# Switches.net
KiCad netlist of a schematic drawn in Altium Designer
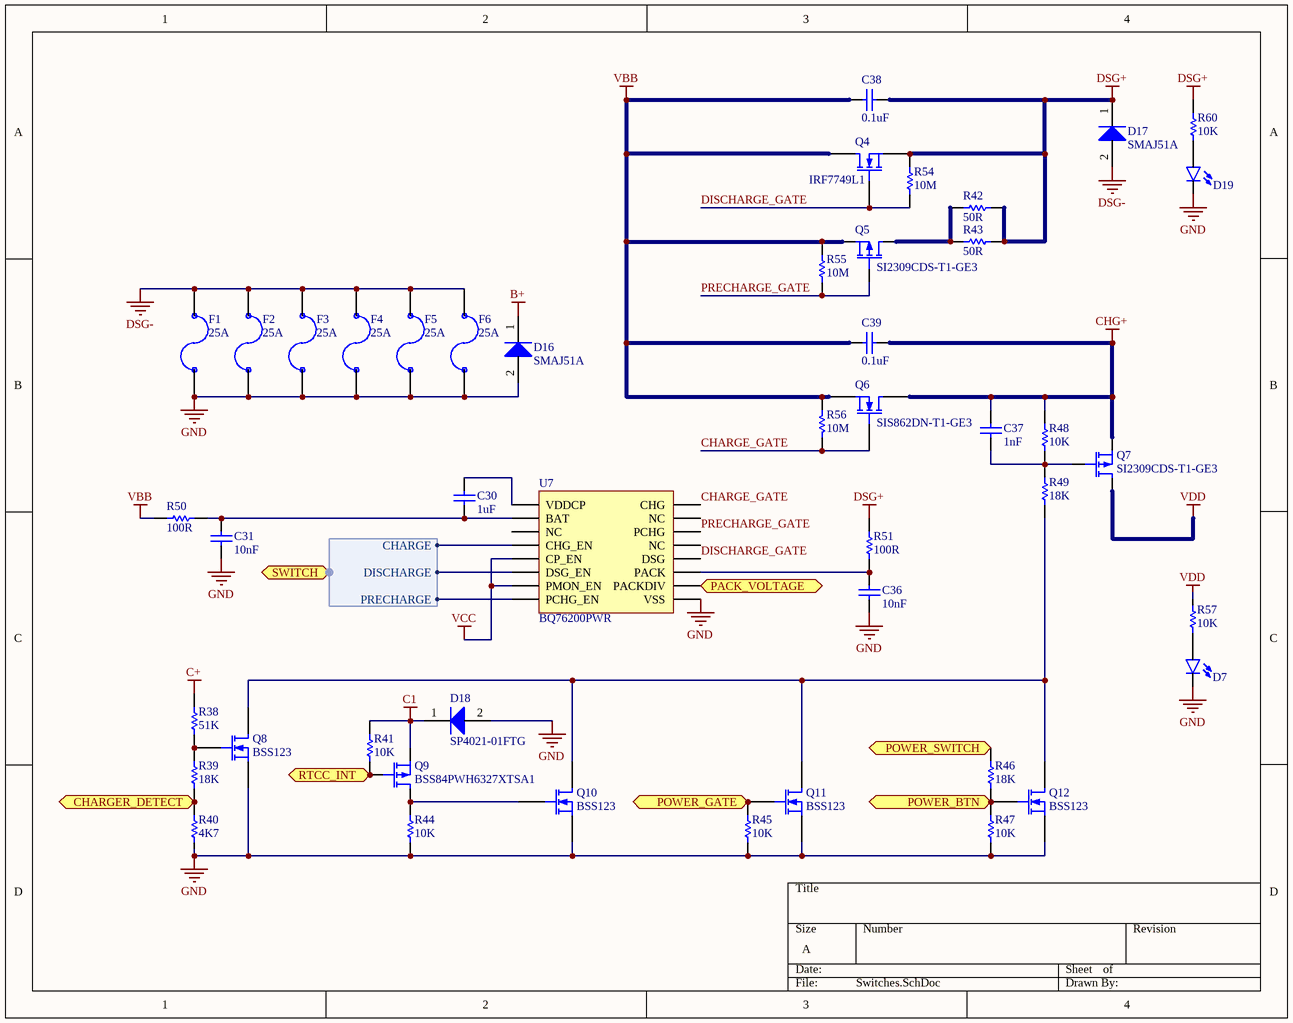
[diagram p0: Switches.SchDoc]

(export (version "E")
  (design (tool "Eeschema 10.0.6"))
  (components
    (comp (ref "C30")
      (value "1uF")
      (footprint "C0603[1608X92]")
      (description "1uF 50V 10% 0603 (1608 Metric)")
      (fields (field (name "TOLERANCE") "10%") (field (name "PARTNUMBER") "GRM188R61H105KAALD"))
      (libsource (lib "Capacitors") (part "CAP_1uF_50V_0603_10%"))
    )
    (comp (ref "C31")
      (value "10nF")
      (footprint "C0402[1005X55]")
      (description "10nF 100V 10% 0402 (1005 Metric)")
      (fields (field (name "TOLERANCE") "10%") (field (name "PARTNUMBER") "C1005X7S2A103K050BB"))
      (libsource (lib "Capacitors") (part "CAP_10nF_100V_0402_10%"))
    )
    (comp (ref "C36")
      (value "10nF")
      (footprint "C0402[1005X55]")
      (description "10nF 100V 10% 0402 (1005 Metric)")
      (fields (field (name "TOLERANCE") "10%") (field (name "PARTNUMBER") "C1005X7S2A103K050BB"))
      (libsource (lib "Capacitors") (part "CAP_10nF_100V_0402_10%"))
    )
    (comp (ref "C37")
      (value "1nF")
      (footprint "C0402[1005X55]")
      (description "1nF 50V 5% 0402 (1005 Metric)")
      (fields (field (name "PARTNUMBER") "GRM1555C1H102JA01D") (field (name "MANUFACTURER") "Murata"))
      (libsource (lib "Capacitors") (part "CAP_1nF_50V_0402_5%"))
    )
    (comp (ref "C38")
      (value "0.1uF")
      (footprint "C0402[1005X55]")
      (description "0.1uF 100V 10% 0402 (1005 Metric)")
      (fields (field (name "PARTNUMBER") "GRM155R62A104KE14D") (field (name "MANUFACTURER") "Murata"))
      (libsource (lib "Capacitors") (part "CAP_0.1uF_100V_0402_10%"))
    )
    (comp (ref "C39")
      (value "0.1uF")
      (footprint "C0402[1005X55]")
      (description "0.1uF 100V 10% 0402 (1005 Metric)")
      (fields (field (name "PARTNUMBER") "GRM155R62A104KE14D") (field (name "MANUFACTURER") "Murata"))
      (libsource (lib "Capacitors") (part "CAP_0.1uF_100V_0402_10%"))
    )
    (comp (ref "D7")
      (value "LED-BLUE")
      (footprint "LED0603")
      (fields (field (name "PARTNUMBER") "LTST-C193TGKT-5A") (field (name "MANUFACTURER") "Lite-On Inc."))
      (libsource (lib "LEDs") (part "LED_0603_GREEN_5mA"))
    )
    (comp (ref "D16")
      (value "SMAJ51A")
      (footprint "DO-214AC")
      (fields (field (name "PARTNUMBER") "SMAJ51A-E3/61") (field (name "MANUFACTURER") "Vishay"))
      (libsource (lib "Diodes") (part "SMAJ51A-E3/61"))
    )
    (comp (ref "D17")
      (value "SMAJ51A")
      (footprint "DO-214AC")
      (fields (field (name "PARTNUMBER") "SMAJ51A-E3/61") (field (name "MANUFACTURER") "Vishay"))
      (libsource (lib "Diodes") (part "SMAJ51A-E3/61"))
    )
    (comp (ref "D18")
      (value "SP4021-01FTG")
      (footprint "SOD-323")
      (fields (field (name "MANUFACTURER") "Littelfuse"))
      (libsource (lib "Diodes-TVS") (part "SP4021-01FTG"))
    )
    (comp (ref "D19")
      (value "LED-BLUE")
      (footprint "LED0603")
      (fields (field (name "PARTNUMBER") "LTST-C193TGKT-5A") (field (name "MANUFACTURER") "Lite-On Inc."))
      (libsource (lib "LEDs") (part "LED_0603_GREEN_5mA"))
    )
    (comp (ref "F1")
      (value "FUSE 1206")
      (footprint "1206_FUSE")
      (description "Surface Mount Fuses UST 1206 FUSE 25A F")
      (fields
        (field (name "PARTNUMBER") "3413.0332.22")
        (field (name "MANUFACTURER") "Schurter")
        (field (name "CURRENT") "25A")
      )
      (libsource (lib "Components") (part "FUSE 1206"))
    )
    (comp (ref "F2")
      (value "FUSE 1206")
      (footprint "1206_FUSE")
      (description "Surface Mount Fuses UST 1206 FUSE 25A F")
      (fields
        (field (name "PARTNUMBER") "3413.0332.22")
        (field (name "MANUFACTURER") "Schurter")
        (field (name "CURRENT") "25A")
      )
      (libsource (lib "Components") (part "FUSE 1206"))
    )
    (comp (ref "F3")
      (value "FUSE 1206")
      (footprint "1206_FUSE")
      (description "Surface Mount Fuses UST 1206 FUSE 25A F")
      (fields
        (field (name "PARTNUMBER") "3413.0332.22")
        (field (name "MANUFACTURER") "Schurter")
        (field (name "CURRENT") "25A")
      )
      (libsource (lib "Components") (part "FUSE 1206"))
    )
    (comp (ref "F4")
      (value "FUSE 1206")
      (footprint "1206_FUSE")
      (description "Surface Mount Fuses UST 1206 FUSE 25A F")
      (fields
        (field (name "PARTNUMBER") "3413.0332.22")
        (field (name "MANUFACTURER") "Schurter")
        (field (name "CURRENT") "25A")
      )
      (libsource (lib "Components") (part "FUSE 1206"))
    )
    (comp (ref "F5")
      (value "FUSE 1206")
      (footprint "1206_FUSE")
      (description "Surface Mount Fuses UST 1206 FUSE 25A F")
      (fields
        (field (name "PARTNUMBER") "3413.0332.22")
        (field (name "MANUFACTURER") "Schurter")
        (field (name "CURRENT") "25A")
      )
      (libsource (lib "Components") (part "FUSE 1206"))
    )
    (comp (ref "F6")
      (value "FUSE 1206")
      (footprint "1206_FUSE")
      (description "Surface Mount Fuses UST 1206 FUSE 25A F")
      (fields
        (field (name "PARTNUMBER") "3413.0332.22")
        (field (name "MANUFACTURER") "Schurter")
        (field (name "CURRENT") "25A")
      )
      (libsource (lib "Components") (part "FUSE 1206"))
    )
    (comp (ref "Q4")
      (value "IRF7749L1")
      (footprint "DIRECTFET-9")
      (description "N-Channel MOSFET")
      (fields
        (field (name "PARTNUMBER") "IRF7749L1TRPBF")
        (field (name "MANUFACTURER") "Infineon Technologies")
      )
      (libsource (lib "MOSFETs") (part "IRF7749L2"))
    )
    (comp (ref "Q5")
      (value "SI2309CDS-T1-GE3")
      (footprint "SOT23-3")
      (description "P-Channel MOSFET")
      (fields (field (name "MANUFACTURER") "Vishay"))
      (libsource (lib "MOSFETs") (part "SI2309CDS-T1-GE3"))
    )
    (comp (ref "Q6")
      (value "SIS862DN-T1-GE3")
      (footprint "PowerPak-1212-8")
      (description "N-Channel MOSFET")
      (fields (field (name "MANUFACTURER") "Vishay"))
      (libsource (lib "MOSFETs") (part "SIS862DN-T1-GE3"))
    )
    (comp (ref "Q7")
      (value "SI2309CDS-T1-GE3")
      (footprint "SOT23-3")
      (description "P-Channel MOSFET")
      (fields (field (name "MANUFACTURER") "Vishay"))
      (libsource (lib "MOSFETs") (part "SI2309CDS-T1-GE3"))
    )
    (comp (ref "Q8")
      (value "BSS123")
      (footprint "SOT323-3")
      (description "N-Channel MOSFET")
      (fields (field (name "PARTNUMBER") "BSS123WQ-7-F") (field (name "MANUFACTURER") "Diodes Incorporated"))
      (libsource (lib "MOSFETs") (part "BSS123WQ-7-F"))
    )
    (comp (ref "Q9")
      (value "BSS84PWH6327XTSA1")
      (footprint "SOT323-3")
      (description "P-Channel MOSFET")
      (fields (field (name "MANUFACTURER") "Infineon"))
      (libsource (lib "MOSFETs") (part "BSS84PW H6327"))
    )
    (comp (ref "Q10")
      (value "BSS123")
      (footprint "SOT323-3")
      (description "N-Channel MOSFET")
      (fields (field (name "PARTNUMBER") "BSS123WQ-7-F") (field (name "MANUFACTURER") "Diodes Incorporated"))
      (libsource (lib "MOSFETs") (part "BSS123WQ-7-F"))
    )
    (comp (ref "Q11")
      (value "BSS123")
      (footprint "SOT323-3")
      (description "N-Channel MOSFET")
      (fields (field (name "PARTNUMBER") "BSS123WQ-7-F") (field (name "MANUFACTURER") "Diodes Incorporated"))
      (libsource (lib "MOSFETs") (part "BSS123WQ-7-F"))
    )
    (comp (ref "Q12")
      (value "BSS123")
      (footprint "SOT323-3")
      (description "N-Channel MOSFET")
      (fields (field (name "PARTNUMBER") "BSS123WQ-7-F") (field (name "MANUFACTURER") "Diodes Incorporated"))
      (libsource (lib "MOSFETs") (part "BSS123WQ-7-F"))
    )
    (comp (ref "R38")
      (value "51K")
      (footprint "R0402[1005]")
      (description "51K 0.063W 1% 0402 (1005 Metric)")
      (fields (field (name "POWER") "0.063W") (field (name "TOLERANCE") "1%"))
      (libsource (lib "Resistors") (part "RES_51K_0402_1%"))
    )
    (comp (ref "R39")
      (value "18K")
      (footprint "R0402[1005]")
      (description "18K 0.063W 1% 0402 (1005 Metric)")
      (fields (field (name "TOLERANCE") "1%") (field (name "POWER") "0.063W"))
      (libsource (lib "Resistors") (part "RES_18K_0402_1%"))
    )
    (comp (ref "R40")
      (value "4K7")
      (footprint "R0402[1005]")
      (description "4K7 0.063W 1% 0402 (1005 Metric)")
      (fields (field (name "TOLERANCE") "1%") (field (name "POWER") "0.063W"))
      (libsource (lib "Resistors") (part "RES_4K7_0402_1%"))
    )
    (comp (ref "R41")
      (value "10K")
      (footprint "R0402[1005]")
      (description "10K 0.063W 1% 0402 (1005 Metric)")
      (fields (field (name "MANUFACTURER") "KOA Speer") (field (name "PARTNUMBER") "RK73H1ETTP1002F"))
      (libsource (lib "Resistors") (part "RES_10K_0402_1%"))
    )
    (comp (ref "R42")
      (value "50R")
      (footprint "R1206[3216]")
      (description "50R 2.4W 2% 1206 (3216 Metric)")
      (fields (field (name "TOLERANCE") "2%") (field (name "POWER") "2.4W"))
      (libsource (lib "Resistors") (part "RES_50R_1206_2%"))
    )
    (comp (ref "R43")
      (value "50R")
      (footprint "R1206[3216]")
      (description "50R 2.4W 2% 1206 (3216 Metric)")
      (fields (field (name "TOLERANCE") "2%") (field (name "POWER") "2.4W"))
      (libsource (lib "Resistors") (part "RES_50R_1206_2%"))
    )
    (comp (ref "R44")
      (value "10K")
      (footprint "R0402[1005]")
      (description "10K 0.063W 1% 0402 (1005 Metric)")
      (fields (field (name "MANUFACTURER") "KOA Speer") (field (name "PARTNUMBER") "RK73H1ETTP1002F"))
      (libsource (lib "Resistors") (part "RES_10K_0402_1%"))
    )
    (comp (ref "R45")
      (value "10K")
      (footprint "R0402[1005]")
      (description "10K 0.063W 1% 0402 (1005 Metric)")
      (fields (field (name "MANUFACTURER") "KOA Speer") (field (name "PARTNUMBER") "RK73H1ETTP1002F"))
      (libsource (lib "Resistors") (part "RES_10K_0402_1%"))
    )
    (comp (ref "R46")
      (value "18K")
      (footprint "R0402[1005]")
      (description "18K 0.063W 1% 0402 (1005 Metric)")
      (fields (field (name "TOLERANCE") "1%") (field (name "POWER") "0.063W"))
      (libsource (lib "Resistors") (part "RES_18K_0402_1%"))
    )
    (comp (ref "R47")
      (value "10K")
      (footprint "R0402[1005]")
      (description "10K 0.063W 1% 0402 (1005 Metric)")
      (fields (field (name "POWER") "0.063W") (field (name "TOLERANCE") "1%"))
      (libsource (lib "Resistors") (part "RES_10K_0402_1%"))
    )
    (comp (ref "R48")
      (value "10K")
      (footprint "R0402[1005]")
      (description "10K 0.063W 1% 0402 (1005 Metric)")
      (fields (field (name "TOLERANCE") "1%") (field (name "POWER") "0.063W"))
      (libsource (lib "Resistors") (part "RES_10K_0402_1%"))
    )
    (comp (ref "R49")
      (value "18K")
      (footprint "R0402[1005]")
      (description "18K 0.063W 1% 0402 (1005 Metric)")
      (fields (field (name "POWER") "0.063W") (field (name "TOLERANCE") "1%"))
      (libsource (lib "Resistors") (part "RES_18K_0402_1%"))
    )
    (comp (ref "R50")
      (value "100R")
      (footprint "R0402[1005]")
      (description "100R 0.063W 1% 0402 (1005 Metric)")
      (fields (field (name "POWER") "0.063W") (field (name "TOLERANCE") "1%"))
      (libsource (lib "Resistors") (part "RES_100R_0402_1%"))
    )
    (comp (ref "R51")
      (value "100R")
      (footprint "R0402[1005]")
      (description "100R 0.063W 1% 0402 (1005 Metric)")
      (fields (field (name "POWER") "0.063W") (field (name "TOLERANCE") "1%"))
      (libsource (lib "Resistors") (part "RES_100R_0402_1%"))
    )
    (comp (ref "R54")
      (value "10M")
      (footprint "R0402[1005]")
      (description "10M 0.063W 1% 0402 (1005 Metric)")
      (fields (field (name "MANUFACTURER") "KOA Speer") (field (name "PARTNUMBER") "RK73H1ETTP1005F"))
      (libsource (lib "Resistors") (part "RES_10M_0402_1%"))
    )
    (comp (ref "R55")
      (value "10M")
      (footprint "R0402[1005]")
      (description "10M 0.063W 1% 0402 (1005 Metric)")
      (fields (field (name "MANUFACTURER") "KOA Speer") (field (name "PARTNUMBER") "RK73H1ETTP1005F"))
      (libsource (lib "Resistors") (part "RES_10M_0402_1%"))
    )
    (comp (ref "R56")
      (value "10M")
      (footprint "R0402[1005]")
      (description "10M 0.063W 1% 0402 (1005 Metric)")
      (fields (field (name "MANUFACTURER") "KOA Speer") (field (name "PARTNUMBER") "RK73H1ETTP1005F"))
      (libsource (lib "Resistors") (part "RES_10M_0402_1%"))
    )
    (comp (ref "R57")
      (value "10K")
      (footprint "R0603[1608]")
      (description "10K 0.25W 1% 0603 (1005 Metric)")
      (fields (field (name "TOLERANCE") "1%") (field (name "POWER") "0.25W"))
      (libsource (lib "Resistors") (part "RES_10K_0603_1%"))
    )
    (comp (ref "R60")
      (value "10K")
      (footprint "R0603[1608]")
      (description "10K 0.25W 1% 0603 (1005 Metric)")
      (fields (field (name "TOLERANCE") "1%") (field (name "POWER") "0.25W"))
      (libsource (lib "Resistors") (part "RES_10K_0603_1%"))
    )
    (comp (ref "U7")
      (value "BQ76200PWR")
      (footprint "TSSOP-16")
      (description "Battery Management Fast high side NCH drive")
      (fields (field (name "MANUFACTURER") "Texas Instruments"))
      (libsource (lib "ICs") (part "BQ76200PWR"))
    )
  )
  (nets
    (net (code "2") (name "/CHARGE") (class "Default")
      (node (ref "U7") (pin "4") (pinfunction "CHG_EN_4") (pintype "passive"))
    )
    (net (code "3") (name "/CHARGER_DETECT") (class "Default")
      (node (ref "R39") (pin "1") (pinfunction "1_1") (pintype "passive"))
      (node (ref "R40") (pin "2") (pinfunction "2_2") (pintype "passive"))
    )
    (net (code "4") (name "/CHARGE_GATE") (class "Default")
      (node (ref "Q6") (pin "2") (pinfunction "G_2") (pintype "passive"))
      (node (ref "R56") (pin "1") (pinfunction "1_1") (pintype "passive"))
      (node (ref "U7") (pin "16") (pinfunction "CHG_16") (pintype "passive"))
    )
    (net (code "5") (name "/DISCHARGE") (class "Default")
      (node (ref "U7") (pin "6") (pinfunction "DSG_EN_6") (pintype "passive"))
    )
    (net (code "6") (name "/DISCHARGE_GATE") (class "Default")
      (node (ref "Q4") (pin "1") (pinfunction "G_1") (pintype "passive"))
      (node (ref "R54") (pin "1") (pinfunction "1_1") (pintype "passive"))
      (node (ref "U7") (pin "12") (pinfunction "DSG_12") (pintype "passive"))
    )
    (net (code "7") (name "/PACK_VOLTAGE") (class "Default")
      (node (ref "U7") (pin "10") (pinfunction "PACKDIV_10") (pintype "passive"))
    )
    (net (code "8") (name "/POWER_BTN") (class "Default")
      (node (ref "Q12") (pin "1") (pinfunction "G_1") (pintype "passive"))
      (node (ref "R46") (pin "1") (pinfunction "1_1") (pintype "passive"))
      (node (ref "R47") (pin "2") (pinfunction "2_2") (pintype "passive"))
    )
    (net (code "9") (name "/POWER_GATE") (class "Default")
      (node (ref "Q11") (pin "1") (pinfunction "G_1") (pintype "passive"))
      (node (ref "R45") (pin "2") (pinfunction "2_2") (pintype "passive"))
    )
    (net (code "10") (name "/POWER_SWITCH") (class "Default")
      (node (ref "R46") (pin "2") (pinfunction "2_2") (pintype "passive"))
    )
    (net (code "11") (name "/PRECHARGE") (class "Default")
      (node (ref "U7") (pin "8") (pinfunction "PCHG_EN_8") (pintype "passive"))
    )
    (net (code "12") (name "/PRECHARGE_GATE") (class "Default")
      (node (ref "Q5") (pin "1") (pinfunction "G_1") (pintype "passive"))
      (node (ref "R55") (pin "1") (pinfunction "1_1") (pintype "passive"))
      (node (ref "U7") (pin "14") (pinfunction "PCHG_14") (pintype "passive"))
    )
    (net (code "13") (name "/RTCC_INT") (class "Default")
      (node (ref "Q9") (pin "1") (pinfunction "G_1") (pintype "passive"))
      (node (ref "R41") (pin "1") (pinfunction "1_1") (pintype "passive"))
    )
    (net (code "15") (name "B+") (class "Default")
      (node (ref "D16") (pin "1") (pinfunction "K_1") (pintype "passive"))
    )
    (net (code "16") (name "C+") (class "Default")
      (node (ref "R38") (pin "2") (pinfunction "2_2") (pintype "passive"))
    )
    (net (code "17") (name "C1") (class "Default")
      (node (ref "D18") (pin "1") (pinfunction "K_1") (pintype "passive"))
      (node (ref "Q9") (pin "2") (pinfunction "S_2") (pintype "passive"))
      (node (ref "R41") (pin "2") (pinfunction "2_2") (pintype "passive"))
    )
    (net (code "18") (name "CHG+") (class "Default")
      (node (ref "C37") (pin "2") (pinfunction "2_2") (pintype "passive"))
      (node (ref "C39") (pin "2") (pinfunction "2_2") (pintype "passive"))
      (node (ref "Q6") (pin "3") (pinfunction "D_3") (pintype "passive"))
      (node (ref "Q7") (pin "3") (pinfunction "S_3") (pintype "passive"))
      (node (ref "R48") (pin "2") (pinfunction "2_2") (pintype "passive"))
    )
    (net (code "19") (name "DSG+") (class "Default")
      (node (ref "C38") (pin "2") (pinfunction "2_2") (pintype "passive"))
      (node (ref "D17") (pin "1") (pinfunction "K_1") (pintype "passive"))
      (node (ref "Q4") (pin "2") (pinfunction "S_2") (pintype "passive"))
      (node (ref "R42") (pin "2") (pinfunction "2_2") (pintype "passive"))
      (node (ref "R43") (pin "2") (pinfunction "2_2") (pintype "passive"))
      (node (ref "R51") (pin "2") (pinfunction "2_2") (pintype "passive"))
      (node (ref "R54") (pin "2") (pinfunction "2_2") (pintype "passive"))
      (node (ref "R60") (pin "2") (pinfunction "2_2") (pintype "passive"))
    )
    (net (code "20") (name "DSG-") (class "Default")
      (node (ref "D17") (pin "2") (pinfunction "A_2") (pintype "passive"))
      (node (ref "F1") (pin "1") (pinfunction "1_1") (pintype "passive"))
      (node (ref "F2") (pin "1") (pinfunction "1_1") (pintype "passive"))
      (node (ref "F3") (pin "1") (pinfunction "1_1") (pintype "passive"))
      (node (ref "F4") (pin "1") (pinfunction "1_1") (pintype "passive"))
      (node (ref "F5") (pin "1") (pinfunction "1_1") (pintype "passive"))
      (node (ref "F6") (pin "1") (pinfunction "1_1") (pintype "passive"))
    )
    (net (code "21") (name "GND") (class "Default")
      (node (ref "C31") (pin "1") (pinfunction "1_1") (pintype "passive"))
      (node (ref "C36") (pin "1") (pinfunction "1_1") (pintype "passive"))
      (node (ref "D16") (pin "2") (pinfunction "A_2") (pintype "passive"))
      (node (ref "D18") (pin "2") (pinfunction "A_2") (pintype "passive"))
      (node (ref "D19") (pin "C") (pinfunction "C_C") (pintype "passive"))
      (node (ref "D7") (pin "C") (pinfunction "C_C") (pintype "passive"))
      (node (ref "F1") (pin "2") (pinfunction "2_2") (pintype "passive"))
      (node (ref "F2") (pin "2") (pinfunction "2_2") (pintype "passive"))
      (node (ref "F3") (pin "2") (pinfunction "2_2") (pintype "passive"))
      (node (ref "F4") (pin "2") (pinfunction "2_2") (pintype "passive"))
      (node (ref "F5") (pin "2") (pinfunction "2_2") (pintype "passive"))
      (node (ref "F6") (pin "2") (pinfunction "2_2") (pintype "passive"))
      (node (ref "Q10") (pin "2") (pinfunction "S_2") (pintype "passive"))
      (node (ref "Q11") (pin "2") (pinfunction "S_2") (pintype "passive"))
      (node (ref "Q12") (pin "2") (pinfunction "S_2") (pintype "passive"))
      (node (ref "Q8") (pin "2") (pinfunction "S_2") (pintype "passive"))
      (node (ref "R40") (pin "1") (pinfunction "1_1") (pintype "passive"))
      (node (ref "R44") (pin "1") (pinfunction "1_1") (pintype "passive"))
      (node (ref "R45") (pin "1") (pinfunction "1_1") (pintype "passive"))
      (node (ref "R47") (pin "1") (pinfunction "1_1") (pintype "passive"))
      (node (ref "U7") (pin "9") (pinfunction "VSS_9") (pintype "passive"))
    )
    (net (code "22") (name "Net-(D7-PadA)") (class "Default")
      (node (ref "D7") (pin "A") (pinfunction "A_A") (pintype "passive"))
      (node (ref "R57") (pin "1") (pinfunction "1_1") (pintype "passive"))
    )
    (net (code "23") (name "Net-(D19-PadA)") (class "Default")
      (node (ref "D19") (pin "A") (pinfunction "A_A") (pintype "passive"))
      (node (ref "R60") (pin "1") (pinfunction "1_1") (pintype "passive"))
    )
    (net (code "24") (name "Net-(Q5-D)") (class "Default")
      (node (ref "Q5") (pin "2") (pinfunction "D_2") (pintype "passive"))
      (node (ref "R42") (pin "1") (pinfunction "1_1") (pintype "passive"))
      (node (ref "R43") (pin "1") (pinfunction "1_1") (pintype "passive"))
    )
    (net (code "25") (name "Net-(Q7-G)") (class "Default")
      (node (ref "C37") (pin "1") (pinfunction "1_1") (pintype "passive"))
      (node (ref "Q7") (pin "1") (pinfunction "G_1") (pintype "passive"))
      (node (ref "R48") (pin "1") (pinfunction "1_1") (pintype "passive"))
      (node (ref "R49") (pin "2") (pinfunction "2_2") (pintype "passive"))
    )
    (net (code "26") (name "Net-(Q8-G)") (class "Default")
      (node (ref "Q8") (pin "1") (pinfunction "G_1") (pintype "passive"))
      (node (ref "R38") (pin "1") (pinfunction "1_1") (pintype "passive"))
      (node (ref "R39") (pin "2") (pinfunction "2_2") (pintype "passive"))
    )
    (net (code "27") (name "Net-(Q10-D)") (class "Default")
      (node (ref "Q10") (pin "3") (pinfunction "D_3") (pintype "passive"))
      (node (ref "Q11") (pin "3") (pinfunction "D_3") (pintype "passive"))
      (node (ref "Q12") (pin "3") (pinfunction "D_3") (pintype "passive"))
      (node (ref "Q8") (pin "3") (pinfunction "D_3") (pintype "passive"))
      (node (ref "R49") (pin "1") (pinfunction "1_1") (pintype "passive"))
    )
    (net (code "28") (name "Net-(Q10-G)") (class "Default")
      (node (ref "Q10") (pin "1") (pinfunction "G_1") (pintype "passive"))
      (node (ref "Q9") (pin "3") (pinfunction "D_3") (pintype "passive"))
      (node (ref "R44") (pin "2") (pinfunction "2_2") (pintype "passive"))
    )
    (net (code "29") (name "Net-(U7-BAT)") (class "Default")
      (node (ref "C30") (pin "1") (pinfunction "1_1") (pintype "passive"))
      (node (ref "C31") (pin "2") (pinfunction "2_2") (pintype "passive"))
      (node (ref "R50") (pin "2") (pinfunction "2_2") (pintype "passive"))
      (node (ref "U7") (pin "2") (pinfunction "BAT_2") (pintype "passive"))
    )
    (net (code "30") (name "Net-(U7-PACK)") (class "Default")
      (node (ref "C36") (pin "2") (pinfunction "2_2") (pintype "passive"))
      (node (ref "R51") (pin "1") (pinfunction "1_1") (pintype "passive"))
      (node (ref "U7") (pin "11") (pinfunction "PACK_11") (pintype "passive"))
    )
    (net (code "31") (name "Net-(U7-VDDCP)") (class "Default")
      (node (ref "C30") (pin "2") (pinfunction "2_2") (pintype "passive"))
      (node (ref "U7") (pin "1") (pinfunction "VDDCP_1") (pintype "passive"))
    )
    (net (code "32") (name "VBB") (class "Default")
      (node (ref "C38") (pin "1") (pinfunction "1_1") (pintype "passive"))
      (node (ref "C39") (pin "1") (pinfunction "1_1") (pintype "passive"))
      (node (ref "Q4") (pin "3") (pinfunction "D_3") (pintype "passive"))
      (node (ref "Q5") (pin "3") (pinfunction "S_3") (pintype "passive"))
      (node (ref "Q6") (pin "1") (pinfunction "S_1") (pintype "passive"))
      (node (ref "R50") (pin "1") (pinfunction "1_1") (pintype "passive"))
      (node (ref "R55") (pin "2") (pinfunction "2_2") (pintype "passive"))
      (node (ref "R56") (pin "2") (pinfunction "2_2") (pintype "passive"))
    )
    (net (code "33") (name "VCC") (class "Default")
      (node (ref "U7") (pin "5") (pinfunction "CP_EN_5") (pintype "passive"))
      (node (ref "U7") (pin "7") (pinfunction "PMON_EN_7") (pintype "passive"))
    )
    (net (code "34") (name "VDD") (class "Default")
      (node (ref "Q7") (pin "2") (pinfunction "D_2") (pintype "passive"))
      (node (ref "R57") (pin "2") (pinfunction "2_2") (pintype "passive"))
    )
    (net (code "35") (name "unconnected-(U7-NC-Pad3)") (class "Default")
      (node (ref "U7") (pin "3") (pinfunction "NC_3") (pintype "passive"))
    )
    (net (code "36") (name "unconnected-(U7-NC-Pad13)") (class "Default")
      (node (ref "U7") (pin "13") (pinfunction "NC_13") (pintype "passive"))
    )
    (net (code "37") (name "unconnected-(U7-NC-Pad15)") (class "Default")
      (node (ref "U7") (pin "15") (pinfunction "NC_15") (pintype "passive"))
    )
  )
)
